# AC_to_DC_12V.net
KiCad netlist of a schematic drawn in Altium Designer
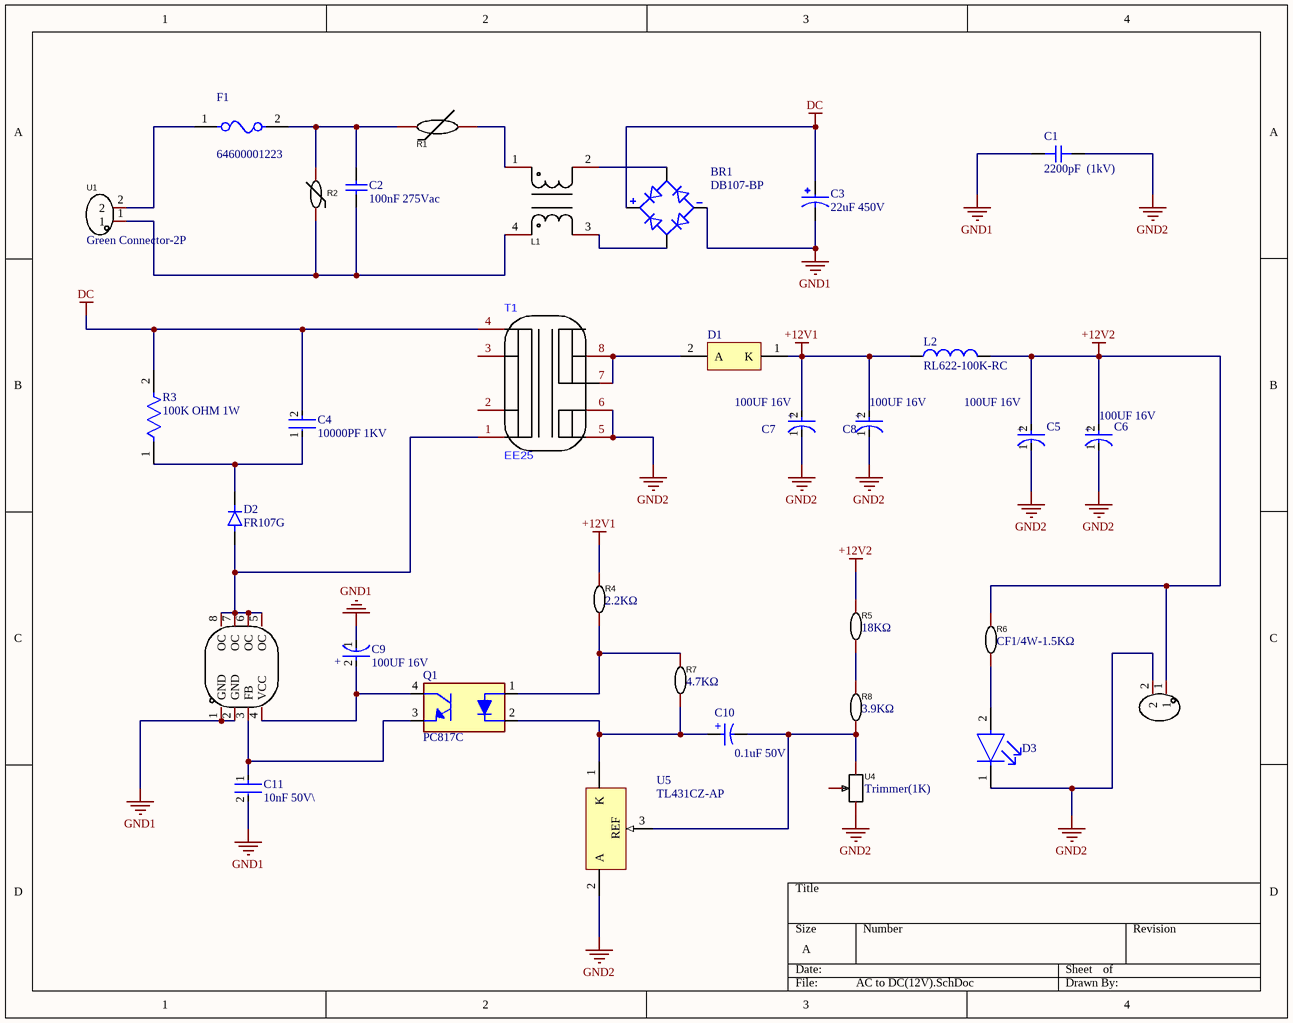
[diagram p0: AC to DC(12V).SchDoc]

(export (version "E")
  (design (tool "Eeschema 10.0.6"))
  (components
    (comp (ref "BR1")
      (value "DB107-BP")
      (footprint "DB107-BP:DIP825W50P509L880H320Q4")
      (fields (field (name "MF") "{'manufacturer': u'Micro Commercial Components'}"))
      (libsource (lib "*") (part "DB107-BP"))
    )
    (comp (ref "C1")
      (value "2200pF  (1kV)")
      (footprint "1206AC222KAT1A:CAPC3216X94N")
      (description "2200pF Â±10% 1000V (1kV) Ceramic Capacitor X7R 1206 (3216 Metric)")
      (fields (field (name "MF") "{'manufacturer': u'AVX'}") (field (name "MP") "1206AC222KAT1A"))
      (libsource (lib "*") (part "1206AC222KAT1A"))
    )
    (comp (ref "C2")
      (value "100nF 275Vac")
      (footprint "WCAP-FTX2_L18W6H12_CS")
      (description "890324025017CS WCAP-FTX2 Film Capacitor 100nF 275Vac")
      (fields (field (name "TOLERANCE") "10%"))
      (libsource (lib "Altium Content Vault") (part "Capacitor_Non-Polarized"))
    )
    (comp (ref "C3")
      (value "22uF 450V")
      (footprint "CAPPRD750W80D1600H2500")
      (fields (field (name "MF") "Panasonic") (field (name "MP") "ECA-2WHG220"))
      (libsource (lib "ECA2WHG220") (part "ECA2WHG220"))
    )
    (comp (ref "C4")
      (value "10000PF 1KV")
      (footprint "FP-562R5GAS10-MFG")
      (description "CAP CER 10000PF 1KV Z5U RADIAL")
      (fields (field (name "TOLERANCE") "20%") (field (name "VOLTAGE") "1kV"))
      (libsource (lib "Altium Content Vault") (part "6d4d395cd7362dd47ce0157d173177e"))
    )
    (comp (ref "C5")
      (value "100UF 16V")
      (footprint "FP-OS-CON-TH-C9-d_0_6-MFG")
      (description "CAP ALUM POLY 100UF 20% 16V T/H")
      (fields (field (name "TOLERANCE") "20%"))
      (libsource (lib "Altium Content Vault") (part "203bc49f2ac43e59fd269a8c329ed05"))
    )
    (comp (ref "C6")
      (value "100UF 16V")
      (footprint "FP-OS-CON-TH-C9-d_0_6-MFG")
      (description "CAP ALUM POLY 100UF 20% 16V T/H")
      (fields (field (name "TOLERANCE") "20%"))
      (libsource (lib "Altium Content Vault") (part "203bc49f2ac43e59fd269a8c329ed05"))
    )
    (comp (ref "C7")
      (value "100UF 16V")
      (footprint "FP-OS-CON-TH-C9-d_0_6-MFG")
      (description "CAP ALUM POLY 100UF 20% 16V T/H")
      (fields (field (name "TOLERANCE") "20%"))
      (libsource (lib "Altium Content Vault") (part "203bc49f2ac43e59fd269a8c329ed05"))
    )
    (comp (ref "C8")
      (value "100UF 16V")
      (footprint "FP-OS-CON-TH-C9-d_0_6-MFG")
      (description "CAP ALUM POLY 100UF 20% 16V T/H")
      (fields (field (name "TOLERANCE") "20%"))
      (libsource (lib "Altium Content Vault") (part "203bc49f2ac43e59fd269a8c329ed05"))
    )
    (comp (ref "C9")
      (value "100UF 16V")
      (footprint "FP-OS-CON-TH-C9-d_0_6-MFG")
      (description "CAP ALUM POLY 100UF 20% 16V T/H")
      (fields (field (name "TOLERANCE") "20%"))
      (libsource (lib "Altium Content Vault") (part "203bc49f2ac43e59fd269a8c329ed05"))
    )
    (comp (ref "C10")
      (value "0.1uF 50V")
      (footprint "WCAP-ATG8_D5H11")
      (description "860010672001 Cap Aluminum Lytic 0.1uF 50V 20% (5 X 11mm) Radial 2mm 3.3mA 2000h 85C")
      (fields (field (name "TOLERANCE") "20%"))
      (libsource (lib "Altium Content Vault") (part "Capacitor_Polarized"))
    )
    (comp (ref "C11")
      (value "10nF 50~{V}")
      (footprint "FP-RCE1K1-2_5-MFG")
      (description "Cap Ceramic Monolithic 10nF 50V 5% Thru-Hole Bulk")
      (fields (field (name "VOLTAGE") "50V") (field (name "TOLERANCE") "5%"))
      (libsource (lib "Altium Content Vault") (part "02cd4be3c70576c341d710602a673aa"))
    )
    (comp (ref "D1")
      (value "MBR160RLG")
      (footprint "ONSC-AXIAL_LEAD-2-59-10_P")
      (description "Rectifier, 2-Pin Axial_Lead, Pb-Free, Tape and Reel")
      (fields (field (name "MANUFACTURER") "On Semiconductor"))
      (libsource (lib "Altium Content Vault") (part "ONSC-D-K1A2-2_A"))
    )
    (comp (ref "D2")
      (value "FR107G")
      (footprint "FR107G:DIOAD1036W78L470D235")
      (fields (field (name "MF") "{'manufacturer': u'Taiwan Semiconductor'}"))
      (libsource (lib "*") (part "FR107G"))
    )
    (comp (ref "D3")
      (value "XQERED-H2-0000-000000301")
      (footprint "FP-XQE-MFG")
      (description "LED XLAMP RED 620NM 1616 SMD")
      (fields
        (field (name "MANUFACTURER") "Cree Inc.")
        (field (name "OCTOPART") "https://octopart.com/xqered-h2-0000-000000301-cree-65034092")
      )
      (libsource (lib "Altium Content Vault") (part "8706943c75ba83719d021d2fdc84c58"))
    )
    (comp (ref "F1")
      (value "64600001223")
      (footprint "FP-64600001223-MFG")
      (description "FUSE BLOCK CART 250V 6.3A PCB")
      (fields
        (field (name "MANUFACTURER") "Littelfuse Inc")
        (field (name "OCTOPART") "https://octopart.com/64600001223-littelfuse-39645661")
      )
      (libsource (lib "Altium Content Vault") (part "5bcf9b9f640e542cf0359d10258e979"))
    )
    (comp (ref "L1")
      (value "UU9.8-10mH")
      (footprint "CMC 10mH")
      (fields (field (name "MANUFACTURER") "FH(风华)"))
      (libsource (lib "CMC 10mH") (part "UU9.8-10mH"))
    )
    (comp (ref "L2")
      (value "RL622-100K-RC")
      (footprint "INDR62-500-1100X850X1100")
      (description "Radial Inductor, 10 uH, +/- 10%, 3 A, -55 to 105 degC, 2-Pin THD, RoHS, Bulk")
      (libsource (lib "Altium Content Vault") (part "IND-2"))
    )
    (comp (ref "Q1")
      (value "PC817C")
      (footprint "PC817C:DIP762W50P254L650H458Q4B")
      (description "High Density Mounting Type Photocoupler")
      (fields (field (name "MF") "{'manufacturer': u'Sharp Corporation'}"))
      (libsource (lib "*") (part "PC817C"))
    )
    (comp (ref "R1")
      (value "MF72 10D7_C72680")
      (footprint "NTC thermistor")
      (fields (field (name "MANUFACTURER") "时恒") (field (name "MANUFACTURER PART") "MF72 10D7"))
      (libsource (lib "NTC thermistor") (part "MF72 10D7_C72680"))
    )
    (comp (ref "R2")
      (value "10D561K_C233178")
      (footprint "varistor")
      (fields (field (name "MANUFACTURER") "RUILON(瑞隆源)") (field (name "MANUFACTURER PART") "10D561K"))
      (libsource (lib "Varistor ") (part "10D561K_C233178"))
    )
    (comp (ref "R3")
      (value "100K OHM 1W")
      (footprint "FP-RR01-MFG")
      (description "RES 100K OHM 5% 1W AXIAL")
      (fields (field (name "TOLERANCE") "5%"))
      (libsource (lib "Altium Content Vault") (part "1029c3af85768c4190bb7ad29bc67b5"))
    )
    (comp (ref "R4")
      (value "2.2KΩ")
      (footprint "CF1/4W-2.2K")
      (fields
        (field (name "MANUFACTURER") "CCO(千志电子)")
        (field (name "MANUFACTURER PART") "CF1/4W-2.2KΩ±5% T")
        (field (name "TOLERANCE") "±5%")
      )
      (libsource (lib "2.2K ") (part "CF1/4W-2.2KΩ±5% T"))
    )
    (comp (ref "R5")
      (value "18KΩ")
      (footprint "CF1/4W-2.2K")
      (fields
        (field (name "MANUFACTURER") "CCO(千志电子)")
        (field (name "MANUFACTURER PART") "CF1/4W-2.2KΩ±5% T")
        (field (name "TOLERANCE") "±5%")
      )
      (libsource (lib "2.2K ") (part "CF1/4W-2.2KΩ±5% T"))
    )
    (comp (ref "R6")
      (value "CF1/4W-1.5KΩ")
      (footprint "CF1/4W-2.2K")
      (fields
        (field (name "MANUFACTURER") "CCO(千志电子)")
        (field (name "MANUFACTURER PART") "CF1/4W-2.2KΩ±5% T")
        (field (name "TOLERANCE") "±5%")
      )
      (libsource (lib "2.2K ") (part "CF1/4W-2.2KΩ±5% T"))
    )
    (comp (ref "R7")
      (value "4.7KΩ")
      (footprint "CF1/4W-2.2K")
      (fields
        (field (name "MANUFACTURER") "CCO(千志电子)")
        (field (name "MANUFACTURER PART") "CF1/4W-2.2KΩ±5% T")
        (field (name "TOLERANCE") "±5%")
      )
      (libsource (lib "2.2K ") (part "CF1/4W-2.2KΩ±5% T"))
    )
    (comp (ref "R8")
      (value "3.9KΩ")
      (footprint "CF1/4W-2.2K")
      (fields
        (field (name "MANUFACTURER") "CCO(千志电子)")
        (field (name "MANUFACTURER PART") "CF1/4W-2.2KΩ±5% T")
        (field (name "TOLERANCE") "±5%")
      )
      (libsource (lib "2.2K ") (part "CF1/4W-2.2KΩ±5% T"))
    )
    (comp (ref "T1")
      (value "EE25")
      (footprint "EE25")
      (libsource (lib "EE25-13-7 transformer") (part "EE25"))
    )
    (comp (ref "U1")
      (value "Green Connector-2P")
      (footprint "KF127-5.0-2P:KF127-5.0-2P")
      (fields (field (name "MANUFACTURER") "KEFA(科发)") (field (name "MANUFACTURER PART") "KF127-5.0-2P"))
      (libsource (lib "KF127-5.0-2P") (part "KF127-5.0-2P"))
    )
    (comp (ref "U2")
      (value "DK124")
      (footprint "AC-DC controller")
      (fields (field (name "MANUFACTURER") "DK(东科半导体)"))
      (libsource (lib "AC-DC controller") (part "DK124"))
    )
    (comp (ref "U3")
      (value "XH-2PA")
      (footprint "XH-2PA white connector")
      (fields (field (name "MANUFACTURER") "ZHOURI(洲日)"))
      (libsource (lib "White connector-2P") (part "XH-2PA"))
    )
    (comp (ref "U4")
      (value "Trimmer(1K)")
      (footprint "trimmer 1K")
      (fields
        (field (name "MANUFACTURER") "BOCHEN(博晨)")
        (field (name "MANUFACTURER PART") "WH06-2C-102(1K)")
        (field (name "TOLERANCE") "±25%")
      )
      (libsource (lib "Trimmer 1K") (part "WH06-2C-102(1K)"))
    )
    (comp (ref "U5")
      (value "TL431CZ-AP")
      (footprint "TO-92")
      (description "Programmable Voltage Reference, 2.5 to 36V, 3-Pin TO-92, Ammopak")
      (libsource (lib "Altium Content Vault") (part "PM-REF-431-SIL3"))
    )
  )
  (nets
    (net (code "1") (name "+12V1") (class "Default")
      (node (ref "C7") (pin "2") (pinfunction "A_2") (pintype "passive"))
      (node (ref "C8") (pin "2") (pinfunction "A_2") (pintype "passive"))
      (node (ref "D1") (pin "1") (pinfunction "K_1") (pintype "passive"))
      (node (ref "L2") (pin "1") (pinfunction "1_1") (pintype "passive"))
      (node (ref "R4") (pin "2") (pinfunction "2_2") (pintype "passive"))
    )
    (net (code "2") (name "+12V2") (class "Default")
      (node (ref "C5") (pin "2") (pinfunction "A_2") (pintype "passive"))
      (node (ref "C6") (pin "2") (pinfunction "A_2") (pintype "passive"))
      (node (ref "L2") (pin "2") (pinfunction "2_2") (pintype "passive"))
      (node (ref "R5") (pin "2") (pinfunction "2_2") (pintype "passive"))
      (node (ref "R6") (pin "2") (pinfunction "2_2") (pintype "passive"))
      (node (ref "U3") (pin "1") (pinfunction "1_1") (pintype "passive"))
    )
    (net (code "3") (name "DC") (class "Default")
      (node (ref "BR1") (pin "1") (pinfunction "POS_1") (pintype "passive"))
      (node (ref "C3") (pin "P") (pinfunction "P_P") (pintype "passive"))
      (node (ref "C4") (pin "2") (pinfunction "2_2") (pintype "passive"))
      (node (ref "R3") (pin "2") (pinfunction "2_2") (pintype "passive"))
      (node (ref "T1") (pin "4") (pinfunction "4_4") (pintype "passive"))
    )
    (net (code "4") (name "GND1") (class "Default")
      (node (ref "BR1") (pin "2") (pinfunction "NEG_2") (pintype "passive"))
      (node (ref "C1") (pin "1") (pinfunction "A_1") (pintype "passive"))
      (node (ref "C11") (pin "2") (pinfunction "2_2") (pintype "passive"))
      (node (ref "C3") (pin "N") (pinfunction "N_N") (pintype "passive"))
      (node (ref "C9") (pin "1") (pinfunction "C_1") (pintype "passive"))
      (node (ref "U2") (pin "1") (pinfunction "GND_1") (pintype "passive"))
      (node (ref "U2") (pin "2") (pinfunction "GND_2") (pintype "passive"))
    )
    (net (code "5") (name "GND2") (class "Default")
      (node (ref "C1") (pin "2") (pinfunction "B_2") (pintype "passive"))
      (node (ref "C5") (pin "1") (pinfunction "C_1") (pintype "passive"))
      (node (ref "C6") (pin "1") (pinfunction "C_1") (pintype "passive"))
      (node (ref "C7") (pin "1") (pinfunction "C_1") (pintype "passive"))
      (node (ref "C8") (pin "1") (pinfunction "C_1") (pintype "passive"))
      (node (ref "D3") (pin "1") (pinfunction "C_1") (pintype "passive"))
      (node (ref "T1") (pin "5") (pinfunction "5_5") (pintype "passive"))
      (node (ref "T1") (pin "6") (pinfunction "6_6") (pintype "passive"))
      (node (ref "U3") (pin "2") (pinfunction "2_2") (pintype "passive"))
      (node (ref "U4") (pin "1") (pinfunction "1_1") (pintype "passive"))
      (node (ref "U5") (pin "2") (pinfunction "A_2") (pintype "passive"))
    )
    (net (code "6") (name "Net-(BR1-AC1)") (class "Default")
      (node (ref "BR1") (pin "3") (pinfunction "AC1_3") (pintype "passive"))
      (node (ref "L1") (pin "2") (pinfunction "2_2") (pintype "passive"))
    )
    (net (code "7") (name "Net-(BR1-AC2)") (class "Default")
      (node (ref "BR1") (pin "4") (pinfunction "AC2_4") (pintype "passive"))
      (node (ref "L1") (pin "3") (pinfunction "3_3") (pintype "passive"))
    )
    (net (code "8") (name "Net-(C2-Pad1)") (class "Default")
      (node (ref "C2") (pin "1") (pinfunction "1_1") (pintype "passive"))
      (node (ref "F1") (pin "2") (pinfunction "2_2") (pintype "passive"))
      (node (ref "R1") (pin "1") (pinfunction "1_1") (pintype "passive"))
      (node (ref "R2") (pin "2") (pinfunction "2_2") (pintype "passive"))
    )
    (net (code "9") (name "Net-(C2-Pad2)") (class "Default")
      (node (ref "C2") (pin "2") (pinfunction "2_2") (pintype "passive"))
      (node (ref "L1") (pin "4") (pinfunction "4_4") (pintype "passive"))
      (node (ref "R2") (pin "1") (pinfunction "1_1") (pintype "passive"))
      (node (ref "U1") (pin "1") (pinfunction "1_1") (pintype "passive"))
    )
    (net (code "10") (name "Net-(C9-A)") (class "Default")
      (node (ref "C9") (pin "2") (pinfunction "A_2") (pintype "passive"))
      (node (ref "Q1") (pin "4") (pinfunction "4_4") (pintype "passive"))
      (node (ref "U2") (pin "4") (pinfunction "VCC_4") (pintype "passive"))
    )
    (net (code "11") (name "Net-(C10-N)") (class "Default")
      (node (ref "C10") (pin "2") (pinfunction "N_2") (pintype "passive"))
      (node (ref "R8") (pin "1") (pinfunction "1_1") (pintype "passive"))
      (node (ref "U4") (pin "3") (pinfunction "3_3") (pintype "passive"))
      (node (ref "U5") (pin "3") (pinfunction "REF_3") (pintype "input"))
    )
    (net (code "12") (name "Net-(C10-P)") (class "Default")
      (node (ref "C10") (pin "1") (pinfunction "P_1") (pintype "passive"))
      (node (ref "Q1") (pin "2") (pinfunction "2_2") (pintype "passive"))
      (node (ref "R7") (pin "1") (pinfunction "1_1") (pintype "passive"))
      (node (ref "U5") (pin "1") (pinfunction "K_1") (pintype "passive"))
    )
    (net (code "13") (name "Net-(D1-A)") (class "Default")
      (node (ref "D1") (pin "2") (pinfunction "A_2") (pintype "passive"))
      (node (ref "T1") (pin "7") (pinfunction "7_7") (pintype "passive"))
      (node (ref "T1") (pin "8") (pinfunction "8_8") (pintype "passive"))
    )
    (net (code "14") (name "Net-(D2-K)") (class "Default")
      (node (ref "C4") (pin "1") (pinfunction "1_1") (pintype "passive"))
      (node (ref "D2") (pin "C") (pinfunction "K_C") (pintype "passive"))
      (node (ref "R3") (pin "1") (pinfunction "1_1") (pintype "passive"))
    )
    (net (code "15") (name "Net-(D2-PadA)") (class "Default")
      (node (ref "D2") (pin "A") (pinfunction "A_A") (pintype "passive"))
      (node (ref "T1") (pin "1") (pinfunction "1_1") (pintype "passive"))
      (node (ref "U2") (pin "5") (pinfunction "OC_5") (pintype "passive"))
      (node (ref "U2") (pin "6") (pinfunction "OC_6") (pintype "passive"))
      (node (ref "U2") (pin "7") (pinfunction "OC_7") (pintype "passive"))
      (node (ref "U2") (pin "8") (pinfunction "OC_8") (pintype "passive"))
    )
    (net (code "16") (name "Net-(D3-A)") (class "Default")
      (node (ref "D3") (pin "2") (pinfunction "A_2") (pintype "passive"))
      (node (ref "R6") (pin "1") (pinfunction "1_1") (pintype "passive"))
    )
    (net (code "17") (name "Net-(F1-Pad1)") (class "Default")
      (node (ref "F1") (pin "1") (pinfunction "1_1") (pintype "passive"))
      (node (ref "U1") (pin "2") (pinfunction "2_2") (pintype "passive"))
    )
    (net (code "18") (name "Net-(L1-Pad1)") (class "Default")
      (node (ref "L1") (pin "1") (pinfunction "1_1") (pintype "passive"))
      (node (ref "R1") (pin "2") (pinfunction "2_2") (pintype "passive"))
    )
    (net (code "19") (name "Net-(Q1-Pad1)") (class "Default")
      (node (ref "Q1") (pin "1") (pinfunction "1_1") (pintype "passive"))
      (node (ref "R4") (pin "1") (pinfunction "1_1") (pintype "passive"))
      (node (ref "R7") (pin "2") (pinfunction "2_2") (pintype "passive"))
    )
    (net (code "20") (name "Net-(R5-Pad1)") (class "Default")
      (node (ref "R5") (pin "1") (pinfunction "1_1") (pintype "passive"))
      (node (ref "R8") (pin "2") (pinfunction "2_2") (pintype "passive"))
    )
    (net (code "21") (name "Net-(U2-FB)") (class "Default")
      (node (ref "C11") (pin "1") (pinfunction "1_1") (pintype "passive"))
      (node (ref "Q1") (pin "3") (pinfunction "3_3") (pintype "passive"))
      (node (ref "U2") (pin "3") (pinfunction "FB_3") (pintype "passive"))
    )
    (net (code "22") (name "unconnected-(T1-Pad2)") (class "Default")
      (node (ref "T1") (pin "2") (pinfunction "2_2") (pintype "passive"))
    )
    (net (code "23") (name "unconnected-(T1-Pad3)") (class "Default")
      (node (ref "T1") (pin "3") (pinfunction "3_3") (pintype "passive"))
    )
    (net (code "24") (name "unconnected-(U4-Pad2)") (class "Default")
      (node (ref "U4") (pin "2") (pinfunction "2_2") (pintype "passive"))
    )
  )
)
